# new_topology.net
KiCad netlist of a schematic drawn in Altium Designer
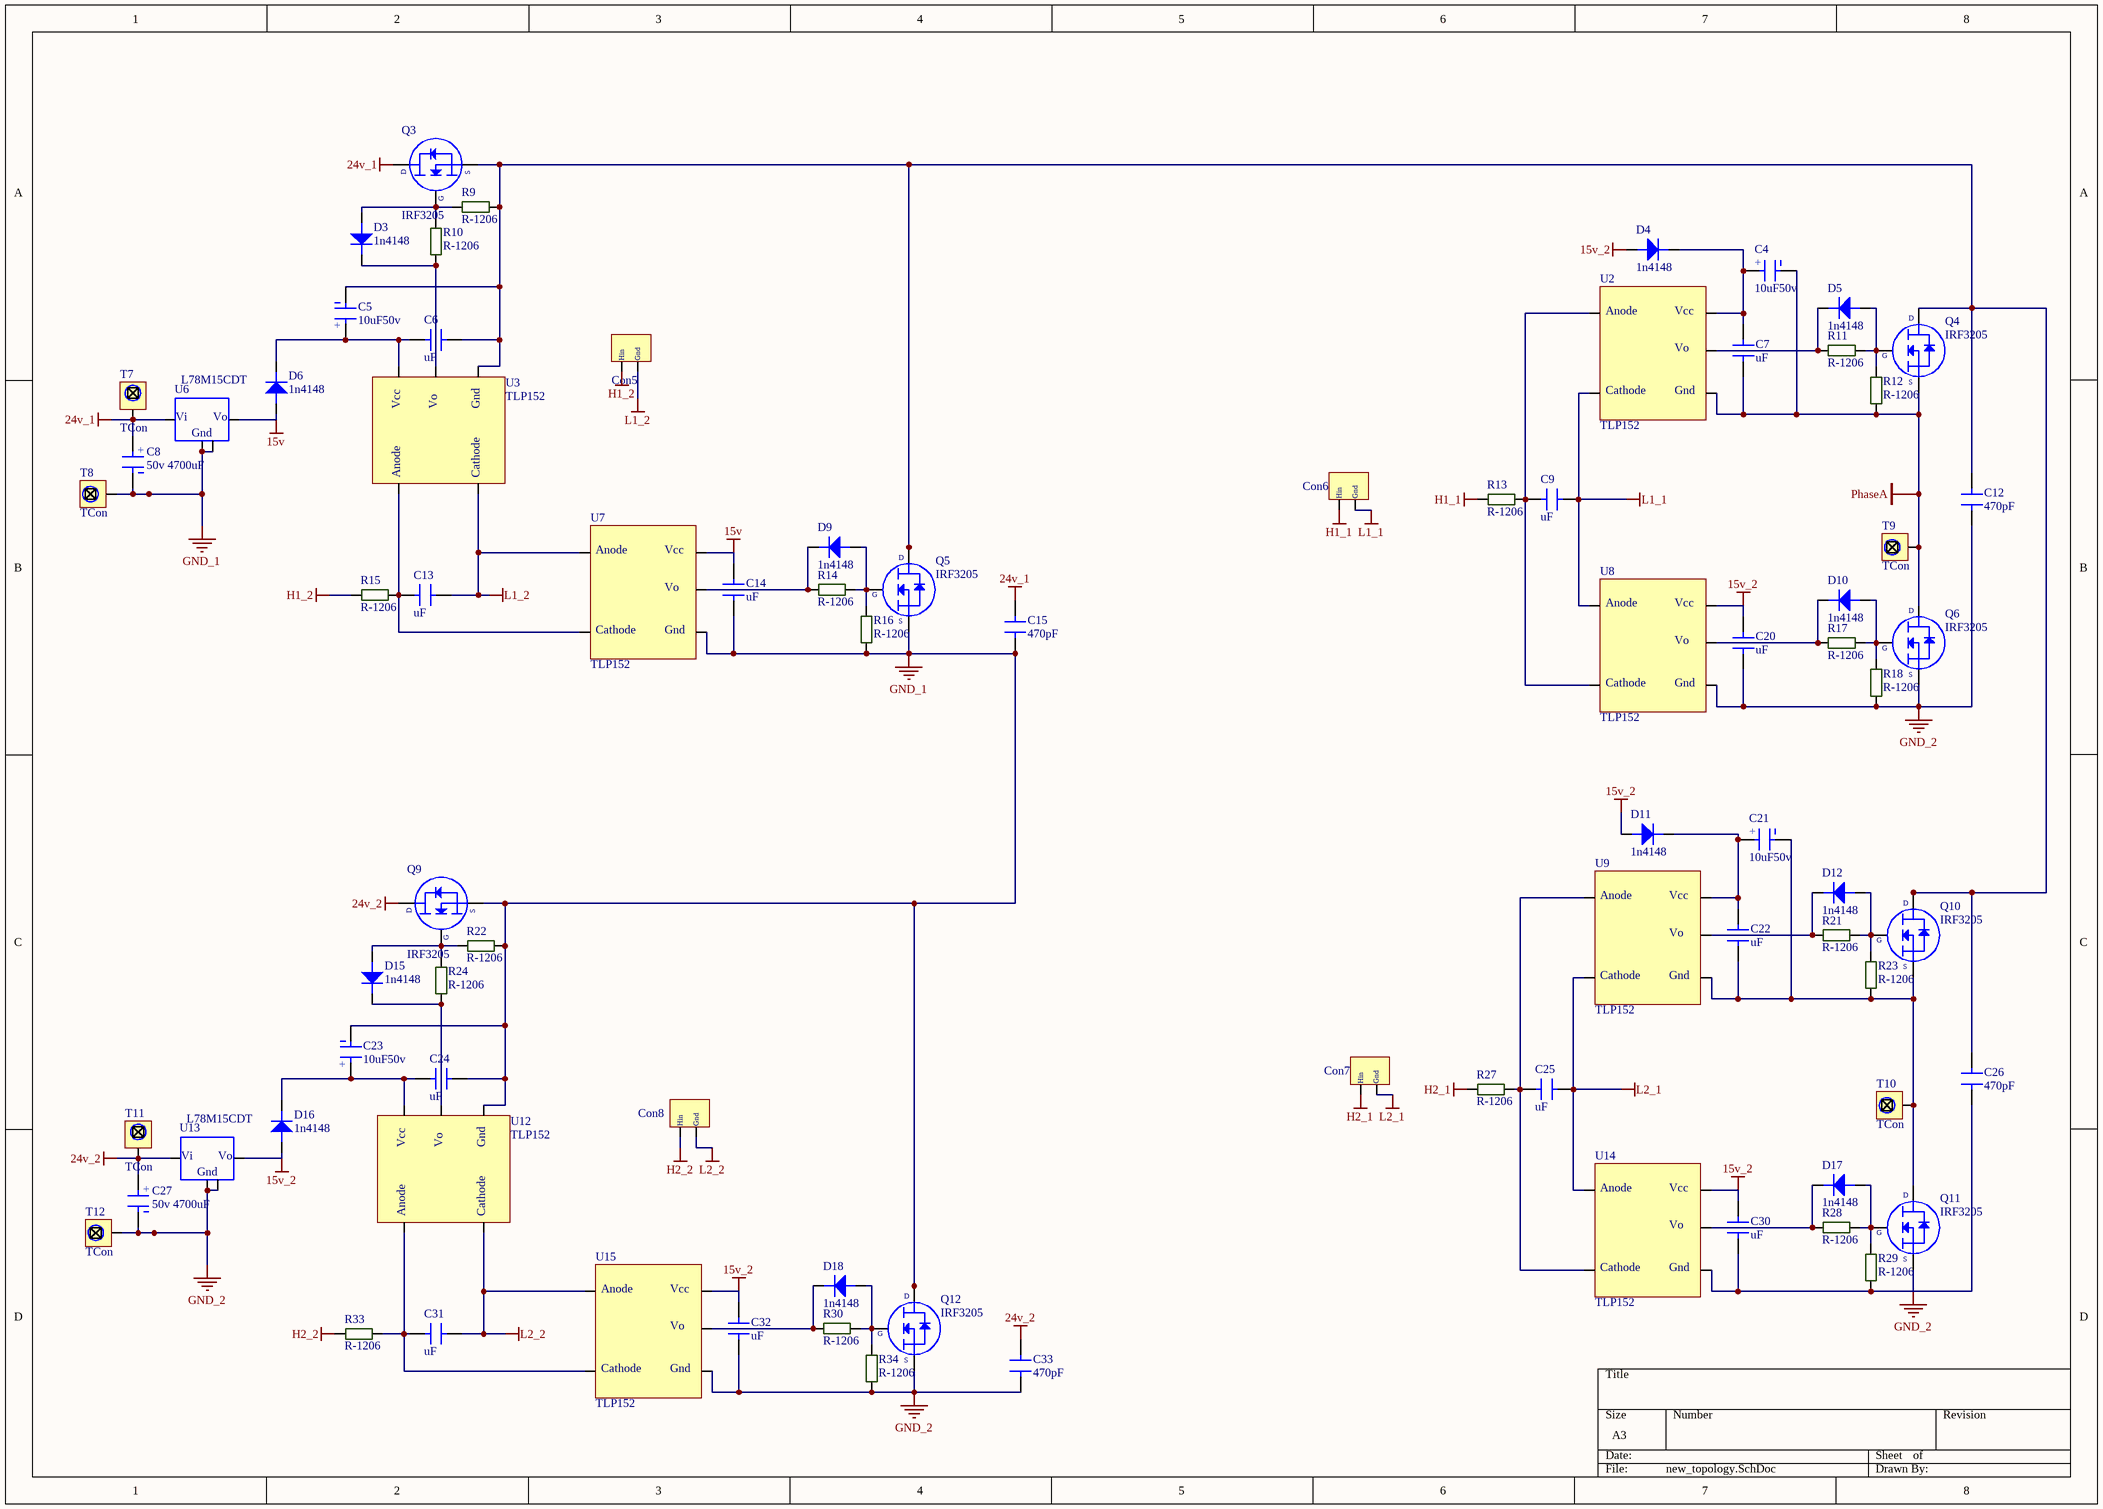
[diagram p0: new_topology.SchDoc]

(export (version "E")
  (design (tool "Eeschema 10.0.6"))
  (components
    (comp (ref "C4")
      (value "10uF50v")
      (footprint "ThreePhaseMLI:4x5.3 cap")
      (description "Aluminum Electrolytic Capacitors - SMD 50volts 10uF 6.3x5.8")
      (fields
        (field (name "MANUFACTURER") "Nichicon")
        (field (name "MANUFACTURER PART NUMBER") "UWD1H100MCL1GS")
      )
      (libsource (lib "ThreePhaseMLI") (part "UWD1H100MCL1GS"))
    )
    (comp (ref "C5")
      (value "10uF50v")
      (footprint "ThreePhaseMLI:4x5.3 cap")
      (description "Aluminum Electrolytic Capacitors - SMD 50volts 10uF 6.3x5.8")
      (fields
        (field (name "MANUFACTURER") "Nichicon")
        (field (name "MANUFACTURER PART NUMBER") "UWD1H100MCL1GS")
      )
      (libsource (lib "ThreePhaseMLI") (part "UWD1H100MCL1GS"))
    )
    (comp (ref "C6")
      (value "uF")
      (footprint "LFI Power Board PcbLib1:C-1206")
      (libsource (lib "ThreePhaseMLI") (part "C-1206"))
    )
    (comp (ref "C7")
      (value "uF")
      (footprint "LFI Power Board PcbLib1:C-1206")
      (libsource (lib "ThreePhaseMLI") (part "C-1206"))
    )
    (comp (ref "C8")
      (value "50v 4700uF")
      (footprint "ThreePhaseMLI:CAPPRD1000W190D2575H3200")
      (description "PKL5-063V472MM450 Aluminum Electrolytic Capacitors - Snap In 63volts 4700uF 20%")
      (fields
        (field (name "MANUFACTURER") "Nichicon")
        (field (name "MANUFACTURER PART NUMBER") "LKS1J472MESZ")
      )
      (libsource (lib "ThreePhaseMLI") (part "Aluminum Electrolytic Capacitors"))
    )
    (comp (ref "C9")
      (value "uF")
      (footprint "LFI Power Board PcbLib1:C-1206")
      (libsource (lib "ThreePhaseMLI") (part "C-1206"))
    )
    (comp (ref "C12")
      (value "470pF")
      (footprint "ThreePhaseMLI:100v 470pF")
      (libsource (lib "ThreePhaseMLI") (part "100v 470p cap"))
    )
    (comp (ref "C13")
      (value "uF")
      (footprint "LFI Power Board PcbLib1:C-1206")
      (libsource (lib "ThreePhaseMLI") (part "C-1206"))
    )
    (comp (ref "C14")
      (value "uF")
      (footprint "LFI Power Board PcbLib1:C-1206")
      (libsource (lib "ThreePhaseMLI") (part "C-1206"))
    )
    (comp (ref "C15")
      (value "470pF")
      (footprint "ThreePhaseMLI:100v 470pF")
      (libsource (lib "ThreePhaseMLI") (part "100v 470p cap"))
    )
    (comp (ref "C20")
      (value "uF")
      (footprint "LFI Power Board PcbLib1:C-1206")
      (libsource (lib "ThreePhaseMLI") (part "C-1206"))
    )
    (comp (ref "C21")
      (value "10uF50v")
      (footprint "ThreePhaseMLI:4x5.3 cap")
      (description "Aluminum Electrolytic Capacitors - SMD 50volts 10uF 6.3x5.8")
      (fields
        (field (name "MANUFACTURER") "Nichicon")
        (field (name "MANUFACTURER PART NUMBER") "UWD1H100MCL1GS")
      )
      (libsource (lib "ThreePhaseMLI") (part "UWD1H100MCL1GS"))
    )
    (comp (ref "C22")
      (value "uF")
      (footprint "LFI Power Board PcbLib1:C-1206")
      (libsource (lib "ThreePhaseMLI") (part "C-1206"))
    )
    (comp (ref "C23")
      (value "10uF50v")
      (footprint "ThreePhaseMLI:4x5.3 cap")
      (description "Aluminum Electrolytic Capacitors - SMD 50volts 10uF 6.3x5.8")
      (fields
        (field (name "MANUFACTURER") "Nichicon")
        (field (name "MANUFACTURER PART NUMBER") "UWD1H100MCL1GS")
      )
      (libsource (lib "ThreePhaseMLI") (part "UWD1H100MCL1GS"))
    )
    (comp (ref "C24")
      (value "uF")
      (footprint "LFI Power Board PcbLib1:C-1206")
      (libsource (lib "ThreePhaseMLI") (part "C-1206"))
    )
    (comp (ref "C25")
      (value "uF")
      (footprint "LFI Power Board PcbLib1:C-1206")
      (libsource (lib "ThreePhaseMLI") (part "C-1206"))
    )
    (comp (ref "C26")
      (value "470pF")
      (footprint "ThreePhaseMLI:100v 470pF")
      (libsource (lib "ThreePhaseMLI") (part "100v 470p cap"))
    )
    (comp (ref "C27")
      (value "50v 4700uF")
      (footprint "ThreePhaseMLI:CAPPRD1000W190D2575H3200")
      (description "PKL5-063V472MM450 Aluminum Electrolytic Capacitors - Snap In 63volts 4700uF 20%")
      (fields
        (field (name "MANUFACTURER") "Nichicon")
        (field (name "MANUFACTURER PART NUMBER") "LKS1J472MESZ")
      )
      (libsource (lib "ThreePhaseMLI") (part "Aluminum Electrolytic Capacitors"))
    )
    (comp (ref "C30")
      (value "uF")
      (footprint "LFI Power Board PcbLib1:C-1206")
      (libsource (lib "ThreePhaseMLI") (part "C-1206"))
    )
    (comp (ref "C31")
      (value "uF")
      (footprint "LFI Power Board PcbLib1:C-1206")
      (libsource (lib "ThreePhaseMLI") (part "C-1206"))
    )
    (comp (ref "C32")
      (value "uF")
      (footprint "LFI Power Board PcbLib1:C-1206")
      (libsource (lib "ThreePhaseMLI") (part "C-1206"))
    )
    (comp (ref "C33")
      (value "470pF")
      (footprint "ThreePhaseMLI:100v 470pF")
      (libsource (lib "ThreePhaseMLI") (part "100v 470p cap"))
    )
    (comp (ref "Con5")
      (value "Connector2")
      (footprint "Conn")
      (libsource (lib "ThreePhaseMLI") (part "Connector2"))
    )
    (comp (ref "Con6")
      (value "Connector2")
      (footprint "Conn")
      (libsource (lib "ThreePhaseMLI") (part "Connector2"))
    )
    (comp (ref "Con7")
      (value "Connector2")
      (footprint "Conn")
      (libsource (lib "ThreePhaseMLI") (part "Connector2"))
    )
    (comp (ref "Con8")
      (value "Connector2")
      (footprint "Conn")
      (libsource (lib "ThreePhaseMLI") (part "Connector2"))
    )
    (comp (ref "D3")
      (value "1n4148")
      (footprint "LFI Power Board PcbLib1:SOD123")
      (description "Diode Small Signal Switching 100V 0.15A 2-Pin SOD-123 T/R")
      (fields
        (field (name "MANUFACTURER") "Vishay")
        (field (name "MANUFACTURER PART NUMBER") "1N4148W-E3-18")
      )
      (libsource (lib "ThreePhaseMLI") (part "1N4148W-E3-18"))
    )
    (comp (ref "D4")
      (value "1n4148")
      (footprint "LFI Power Board PcbLib1:SOD123")
      (description "Diode Small Signal Switching 100V 0.15A 2-Pin SOD-123 T/R")
      (fields
        (field (name "MANUFACTURER") "Vishay")
        (field (name "MANUFACTURER PART NUMBER") "1N4148W-E3-18")
      )
      (libsource (lib "ThreePhaseMLI") (part "1N4148W-E3-18"))
    )
    (comp (ref "D5")
      (value "1n4148")
      (footprint "LFI Power Board PcbLib1:SOD123")
      (description "Diode Small Signal Switching 100V 0.15A 2-Pin SOD-123 T/R")
      (fields
        (field (name "MANUFACTURER") "Vishay")
        (field (name "MANUFACTURER PART NUMBER") "1N4148W-E3-18")
      )
      (libsource (lib "ThreePhaseMLI") (part "1N4148W-E3-18"))
    )
    (comp (ref "D6")
      (value "1n4148")
      (footprint "LFI Power Board PcbLib1:SOD123")
      (description "Diode Small Signal Switching 100V 0.15A 2-Pin SOD-123 T/R")
      (fields
        (field (name "MANUFACTURER") "Vishay")
        (field (name "MANUFACTURER PART NUMBER") "1N4148W-E3-18")
      )
      (libsource (lib "ThreePhaseMLI") (part "1N4148W-E3-18"))
    )
    (comp (ref "D9")
      (value "1n4148")
      (footprint "LFI Power Board PcbLib1:SOD123")
      (description "Diode Small Signal Switching 100V 0.15A 2-Pin SOD-123 T/R")
      (fields
        (field (name "MANUFACTURER") "Vishay")
        (field (name "MANUFACTURER PART NUMBER") "1N4148W-E3-18")
      )
      (libsource (lib "ThreePhaseMLI") (part "1N4148W-E3-18"))
    )
    (comp (ref "D10")
      (value "1n4148")
      (footprint "LFI Power Board PcbLib1:SOD123")
      (description "Diode Small Signal Switching 100V 0.15A 2-Pin SOD-123 T/R")
      (fields
        (field (name "MANUFACTURER") "Vishay")
        (field (name "MANUFACTURER PART NUMBER") "1N4148W-E3-18")
      )
      (libsource (lib "ThreePhaseMLI") (part "1N4148W-E3-18"))
    )
    (comp (ref "D11")
      (value "1n4148")
      (footprint "LFI Power Board PcbLib1:SOD123")
      (description "Diode Small Signal Switching 100V 0.15A 2-Pin SOD-123 T/R")
      (fields
        (field (name "MANUFACTURER") "Vishay")
        (field (name "MANUFACTURER PART NUMBER") "1N4148W-E3-18")
      )
      (libsource (lib "ThreePhaseMLI") (part "1N4148W-E3-18"))
    )
    (comp (ref "D12")
      (value "1n4148")
      (footprint "LFI Power Board PcbLib1:SOD123")
      (description "Diode Small Signal Switching 100V 0.15A 2-Pin SOD-123 T/R")
      (fields
        (field (name "MANUFACTURER") "Vishay")
        (field (name "MANUFACTURER PART NUMBER") "1N4148W-E3-18")
      )
      (libsource (lib "ThreePhaseMLI") (part "1N4148W-E3-18"))
    )
    (comp (ref "D15")
      (value "1n4148")
      (footprint "LFI Power Board PcbLib1:SOD123")
      (description "Diode Small Signal Switching 100V 0.15A 2-Pin SOD-123 T/R")
      (fields
        (field (name "MANUFACTURER") "Vishay")
        (field (name "MANUFACTURER PART NUMBER") "1N4148W-E3-18")
      )
      (libsource (lib "ThreePhaseMLI") (part "1N4148W-E3-18"))
    )
    (comp (ref "D16")
      (value "1n4148")
      (footprint "LFI Power Board PcbLib1:SOD123")
      (description "Diode Small Signal Switching 100V 0.15A 2-Pin SOD-123 T/R")
      (fields
        (field (name "MANUFACTURER") "Vishay")
        (field (name "MANUFACTURER PART NUMBER") "1N4148W-E3-18")
      )
      (libsource (lib "ThreePhaseMLI") (part "1N4148W-E3-18"))
    )
    (comp (ref "D17")
      (value "1n4148")
      (footprint "LFI Power Board PcbLib1:SOD123")
      (description "Diode Small Signal Switching 100V 0.15A 2-Pin SOD-123 T/R")
      (fields
        (field (name "MANUFACTURER") "Vishay")
        (field (name "MANUFACTURER PART NUMBER") "1N4148W-E3-18")
      )
      (libsource (lib "ThreePhaseMLI") (part "1N4148W-E3-18"))
    )
    (comp (ref "D18")
      (value "1n4148")
      (footprint "LFI Power Board PcbLib1:SOD123")
      (description "Diode Small Signal Switching 100V 0.15A 2-Pin SOD-123 T/R")
      (fields
        (field (name "MANUFACTURER") "Vishay")
        (field (name "MANUFACTURER PART NUMBER") "1N4148W-E3-18")
      )
      (libsource (lib "ThreePhaseMLI") (part "1N4148W-E3-18"))
    )
    (comp (ref "Q3")
      (value "IRF3205")
      (footprint "LFI Power Board PcbLib1:DPAK_TO263")
      (description "MOSFET N-CH 55V 110A D2PAK")
      (fields
        (field (name "MANUFACTURER") "Infineon")
        (field (name "MANUFACTURER PART NUMBER") "IRF3205STRLPBF")
      )
      (libsource (lib "ThreePhaseMLI") (part "IRF3205STRLPBF"))
    )
    (comp (ref "Q4")
      (value "IRF3205")
      (footprint "LFI Power Board PcbLib1:DPAK_TO263")
      (description "MOSFET N-CH 55V 110A D2PAK")
      (fields
        (field (name "MANUFACTURER") "Infineon")
        (field (name "MANUFACTURER PART NUMBER") "IRF3205STRLPBF")
      )
      (libsource (lib "ThreePhaseMLI") (part "IRF3205STRLPBF"))
    )
    (comp (ref "Q5")
      (value "IRF3205")
      (footprint "LFI Power Board PcbLib1:DPAK_TO263")
      (description "MOSFET N-CH 55V 110A D2PAK")
      (fields
        (field (name "MANUFACTURER") "Infineon")
        (field (name "MANUFACTURER PART NUMBER") "IRF3205STRLPBF")
      )
      (libsource (lib "ThreePhaseMLI") (part "IRF3205STRLPBF"))
    )
    (comp (ref "Q6")
      (value "IRF3205")
      (footprint "LFI Power Board PcbLib1:DPAK_TO263")
      (description "MOSFET N-CH 55V 110A D2PAK")
      (fields
        (field (name "MANUFACTURER") "Infineon")
        (field (name "MANUFACTURER PART NUMBER") "IRF3205STRLPBF")
      )
      (libsource (lib "ThreePhaseMLI") (part "IRF3205STRLPBF"))
    )
    (comp (ref "Q9")
      (value "IRF3205")
      (footprint "LFI Power Board PcbLib1:DPAK_TO263")
      (description "MOSFET N-CH 55V 110A D2PAK")
      (fields
        (field (name "MANUFACTURER") "Infineon")
        (field (name "MANUFACTURER PART NUMBER") "IRF3205STRLPBF")
      )
      (libsource (lib "ThreePhaseMLI") (part "IRF3205STRLPBF"))
    )
    (comp (ref "Q10")
      (value "IRF3205")
      (footprint "LFI Power Board PcbLib1:DPAK_TO263")
      (description "MOSFET N-CH 55V 110A D2PAK")
      (fields
        (field (name "MANUFACTURER") "Infineon")
        (field (name "MANUFACTURER PART NUMBER") "IRF3205STRLPBF")
      )
      (libsource (lib "ThreePhaseMLI") (part "IRF3205STRLPBF"))
    )
    (comp (ref "Q11")
      (value "IRF3205")
      (footprint "LFI Power Board PcbLib1:DPAK_TO263")
      (description "MOSFET N-CH 55V 110A D2PAK")
      (fields
        (field (name "MANUFACTURER") "Infineon")
        (field (name "MANUFACTURER PART NUMBER") "IRF3205STRLPBF")
      )
      (libsource (lib "ThreePhaseMLI") (part "IRF3205STRLPBF"))
    )
    (comp (ref "Q12")
      (value "IRF3205")
      (footprint "LFI Power Board PcbLib1:DPAK_TO263")
      (description "MOSFET N-CH 55V 110A D2PAK")
      (fields
        (field (name "MANUFACTURER") "Infineon")
        (field (name "MANUFACTURER PART NUMBER") "IRF3205STRLPBF")
      )
      (libsource (lib "ThreePhaseMLI") (part "IRF3205STRLPBF"))
    )
    (comp (ref "R9")
      (value "R-1206")
      (footprint "LFI Power Board PcbLib1:R-1206")
      (description "Res1206")
      (libsource (lib "ThreePhaseMLI") (part "R-1206"))
    )
    (comp (ref "R10")
      (value "R-1206")
      (footprint "LFI Power Board PcbLib1:R-1206")
      (description "Res1206")
      (libsource (lib "ThreePhaseMLI") (part "R-1206"))
    )
    (comp (ref "R11")
      (value "R-1206")
      (footprint "LFI Power Board PcbLib1:R-1206")
      (description "Res1206")
      (libsource (lib "ThreePhaseMLI") (part "R-1206"))
    )
    (comp (ref "R12")
      (value "R-1206")
      (footprint "LFI Power Board PcbLib1:R-1206")
      (description "Res1206")
      (libsource (lib "ThreePhaseMLI") (part "R-1206"))
    )
    (comp (ref "R13")
      (value "R-1206")
      (footprint "LFI Power Board PcbLib1:R-1206")
      (description "Res1206")
      (libsource (lib "ThreePhaseMLI") (part "R-1206"))
    )
    (comp (ref "R14")
      (value "R-1206")
      (footprint "LFI Power Board PcbLib1:R-1206")
      (description "Res1206")
      (libsource (lib "ThreePhaseMLI") (part "R-1206"))
    )
    (comp (ref "R15")
      (value "R-1206")
      (footprint "LFI Power Board PcbLib1:R-1206")
      (description "Res1206")
      (libsource (lib "ThreePhaseMLI") (part "R-1206"))
    )
    (comp (ref "R16")
      (value "R-1206")
      (footprint "LFI Power Board PcbLib1:R-1206")
      (description "Res1206")
      (libsource (lib "ThreePhaseMLI") (part "R-1206"))
    )
    (comp (ref "R17")
      (value "R-1206")
      (footprint "LFI Power Board PcbLib1:R-1206")
      (description "Res1206")
      (libsource (lib "ThreePhaseMLI") (part "R-1206"))
    )
    (comp (ref "R18")
      (value "R-1206")
      (footprint "LFI Power Board PcbLib1:R-1206")
      (description "Res1206")
      (libsource (lib "ThreePhaseMLI") (part "R-1206"))
    )
    (comp (ref "R21")
      (value "R-1206")
      (footprint "LFI Power Board PcbLib1:R-1206")
      (description "Res1206")
      (libsource (lib "ThreePhaseMLI") (part "R-1206"))
    )
    (comp (ref "R22")
      (value "R-1206")
      (footprint "LFI Power Board PcbLib1:R-1206")
      (description "Res1206")
      (libsource (lib "ThreePhaseMLI") (part "R-1206"))
    )
    (comp (ref "R23")
      (value "R-1206")
      (footprint "LFI Power Board PcbLib1:R-1206")
      (description "Res1206")
      (libsource (lib "ThreePhaseMLI") (part "R-1206"))
    )
    (comp (ref "R24")
      (value "R-1206")
      (footprint "LFI Power Board PcbLib1:R-1206")
      (description "Res1206")
      (libsource (lib "ThreePhaseMLI") (part "R-1206"))
    )
    (comp (ref "R27")
      (value "R-1206")
      (footprint "LFI Power Board PcbLib1:R-1206")
      (description "Res1206")
      (libsource (lib "ThreePhaseMLI") (part "R-1206"))
    )
    (comp (ref "R28")
      (value "R-1206")
      (footprint "LFI Power Board PcbLib1:R-1206")
      (description "Res1206")
      (libsource (lib "ThreePhaseMLI") (part "R-1206"))
    )
    (comp (ref "R29")
      (value "R-1206")
      (footprint "LFI Power Board PcbLib1:R-1206")
      (description "Res1206")
      (libsource (lib "ThreePhaseMLI") (part "R-1206"))
    )
    (comp (ref "R30")
      (value "R-1206")
      (footprint "LFI Power Board PcbLib1:R-1206")
      (description "Res1206")
      (libsource (lib "ThreePhaseMLI") (part "R-1206"))
    )
    (comp (ref "R33")
      (value "R-1206")
      (footprint "LFI Power Board PcbLib1:R-1206")
      (description "Res1206")
      (libsource (lib "ThreePhaseMLI") (part "R-1206"))
    )
    (comp (ref "R34")
      (value "R-1206")
      (footprint "LFI Power Board PcbLib1:R-1206")
      (description "Res1206")
      (libsource (lib "ThreePhaseMLI") (part "R-1206"))
    )
    (comp (ref "T7")
      (value "TCon")
      (footprint "LFI Power Board PcbLib1:tCon")
      (libsource (lib "ThreePhaseMLI") (part "Terminal Connector"))
    )
    (comp (ref "T8")
      (value "TCon")
      (footprint "LFI Power Board PcbLib1:tCon")
      (libsource (lib "") (part "Terminal Connector_1"))
    )
    (comp (ref "T9")
      (value "TCon")
      (footprint "LFI Power Board PcbLib1:tCon")
      (libsource (lib "") (part "Terminal Connector_1"))
    )
    (comp (ref "T10")
      (value "TCon")
      (footprint "LFI Power Board PcbLib1:tCon")
      (libsource (lib "") (part "Terminal Connector_1"))
    )
    (comp (ref "T11")
      (value "TCon")
      (footprint "LFI Power Board PcbLib1:tCon")
      (libsource (lib "ThreePhaseMLI") (part "Terminal Connector"))
    )
    (comp (ref "T12")
      (value "TCon")
      (footprint "LFI Power Board PcbLib1:tCon")
      (libsource (lib "") (part "Terminal Connector_1"))
    )
    (comp (ref "U2")
      (value "TLP152")
      (footprint "TLP152")
      (description "OPTOISO 3.75KV GATE DRIVER 6SO-5")
      (fields
        (field (name "MANUFACTURER") "Toshiba")
        (field (name "MANUFACTURER PART NUMBER") "TLP152(TPL,E")
      )
      (libsource (lib "ThreePhaseMLI") (part "TLP152(TPL,E"))
    )
    (comp (ref "U3")
      (value "TLP152")
      (footprint "TLP152")
      (description "OPTOISO 3.75KV GATE DRIVER 6SO-5")
      (fields
        (field (name "MANUFACTURER") "Toshiba")
        (field (name "MANUFACTURER PART NUMBER") "TLP152(TPL,E")
      )
      (libsource (lib "") (part "TLP152(TPL,E_1"))
    )
    (comp (ref "U6")
      (value "L78M15CDT")
      (footprint "ThreePhaseMLI:TO-252")
      (description "Linear Voltage Regulators 15V 0.5A Positive")
      (fields (field (name "MANUFACTURER") "STMicroelectronics"))
      (libsource (lib "ThreePhaseMLI") (part "L78M15CDT"))
    )
    (comp (ref "U7")
      (value "TLP152")
      (footprint "TLP152")
      (description "OPTOISO 3.75KV GATE DRIVER 6SO-5")
      (fields
        (field (name "MANUFACTURER") "Toshiba")
        (field (name "MANUFACTURER PART NUMBER") "TLP152(TPL,E")
      )
      (libsource (lib "ThreePhaseMLI") (part "TLP152(TPL,E"))
    )
    (comp (ref "U8")
      (value "TLP152")
      (footprint "TLP152")
      (description "OPTOISO 3.75KV GATE DRIVER 6SO-5")
      (fields
        (field (name "MANUFACTURER") "Toshiba")
        (field (name "MANUFACTURER PART NUMBER") "TLP152(TPL,E")
      )
      (libsource (lib "ThreePhaseMLI") (part "TLP152(TPL,E"))
    )
    (comp (ref "U9")
      (value "TLP152")
      (footprint "TLP152")
      (description "OPTOISO 3.75KV GATE DRIVER 6SO-5")
      (fields
        (field (name "MANUFACTURER") "Toshiba")
        (field (name "MANUFACTURER PART NUMBER") "TLP152(TPL,E")
      )
      (libsource (lib "ThreePhaseMLI") (part "TLP152(TPL,E"))
    )
    (comp (ref "U12")
      (value "TLP152")
      (footprint "TLP152")
      (description "OPTOISO 3.75KV GATE DRIVER 6SO-5")
      (fields
        (field (name "MANUFACTURER") "Toshiba")
        (field (name "MANUFACTURER PART NUMBER") "TLP152(TPL,E")
      )
      (libsource (lib "") (part "TLP152(TPL,E_1"))
    )
    (comp (ref "U13")
      (value "L78M15CDT")
      (footprint "ThreePhaseMLI:TO-252")
      (description "Linear Voltage Regulators 15V 0.5A Positive")
      (fields (field (name "MANUFACTURER") "STMicroelectronics"))
      (libsource (lib "ThreePhaseMLI") (part "L78M15CDT"))
    )
    (comp (ref "U14")
      (value "TLP152")
      (footprint "TLP152")
      (description "OPTOISO 3.75KV GATE DRIVER 6SO-5")
      (fields
        (field (name "MANUFACTURER") "Toshiba")
        (field (name "MANUFACTURER PART NUMBER") "TLP152(TPL,E")
      )
      (libsource (lib "ThreePhaseMLI") (part "TLP152(TPL,E"))
    )
    (comp (ref "U15")
      (value "TLP152")
      (footprint "TLP152")
      (description "OPTOISO 3.75KV GATE DRIVER 6SO-5")
      (fields
        (field (name "MANUFACTURER") "Toshiba")
        (field (name "MANUFACTURER PART NUMBER") "TLP152(TPL,E")
      )
      (libsource (lib "ThreePhaseMLI") (part "TLP152(TPL,E"))
    )
  )
  (nets
    (net (code "1") (name "15v") (class "Default")
      (node (ref "C14") (pin "2") (pinfunction "2_2") (pintype "passive"))
      (node (ref "D6") (pin "a") (pinfunction "a_a") (pintype "passive"))
      (node (ref "U6") (pin "3") (pinfunction "3_3") (pintype "passive"))
      (node (ref "U7") (pin "5") (pinfunction "5_5") (pintype "passive"))
    )
    (net (code "2") (name "15v_2") (class "Default")
      (node (ref "C20") (pin "2") (pinfunction "2_2") (pintype "passive"))
      (node (ref "C30") (pin "2") (pinfunction "2_2") (pintype "passive"))
      (node (ref "C32") (pin "2") (pinfunction "2_2") (pintype "passive"))
      (node (ref "D11") (pin "a") (pinfunction "a_a") (pintype "passive"))
      (node (ref "D16") (pin "a") (pinfunction "a_a") (pintype "passive"))
      (node (ref "D4") (pin "a") (pinfunction "a_a") (pintype "passive"))
      (node (ref "U13") (pin "3") (pinfunction "3_3") (pintype "passive"))
      (node (ref "U14") (pin "5") (pinfunction "5_5") (pintype "passive"))
      (node (ref "U15") (pin "5") (pinfunction "5_5") (pintype "passive"))
      (node (ref "U8") (pin "5") (pinfunction "5_5") (pintype "passive"))
    )
    (net (code "3") (name "24v_1") (class "Default")
      (node (ref "C15") (pin "1") (pinfunction "1_1") (pintype "passive"))
      (node (ref "C8") (pin "2") (pinfunction "2_2") (pintype "passive"))
      (node (ref "Q3") (pin "3") (pinfunction "3_3") (pintype "passive"))
      (node (ref "T7") (pin "1") (pinfunction "1_1") (pintype "passive"))
      (node (ref "U6") (pin "1") (pinfunction "1_1") (pintype "passive"))
    )
    (net (code "4") (name "24v_2") (class "Default")
      (node (ref "C27") (pin "2") (pinfunction "2_2") (pintype "passive"))
      (node (ref "C33") (pin "1") (pinfunction "1_1") (pintype "passive"))
      (node (ref "Q9") (pin "3") (pinfunction "3_3") (pintype "passive"))
      (node (ref "T11") (pin "1") (pinfunction "1_1") (pintype "passive"))
      (node (ref "U13") (pin "1") (pinfunction "1_1") (pintype "passive"))
    )
    (net (code "5") (name "GND_1") (class "Default")
      (node (ref "C14") (pin "1") (pinfunction "1_1") (pintype "passive"))
      (node (ref "C15") (pin "2") (pinfunction "2_2") (pintype "passive"))
      (node (ref "C23") (pin "2") (pinfunction "2_2") (pintype "passive"))
      (node (ref "C24") (pin "1") (pinfunction "1_1") (pintype "passive"))
      (node (ref "C8") (pin "1") (pinfunction "1_1") (pintype "passive"))
      (node (ref "Q12") (pin "3") (pinfunction "3_3") (pintype "passive"))
      (node (ref "Q5") (pin "2") (pinfunction "2_2") (pintype "passive"))
      (node (ref "Q9") (pin "2") (pinfunction "2_2") (pintype "passive"))
      (node (ref "R16") (pin "1") (pinfunction "1_1") (pintype "passive"))
      (node (ref "R22") (pin "1") (pinfunction "1_1") (pintype "passive"))
      (node (ref "T8") (pin "1") (pinfunction "1_1") (pintype "passive"))
      (node (ref "U12") (pin "3") (pinfunction "3_3") (pintype "passive"))
      (node (ref "U6") (pin "2") (pinfunction "2_2") (pintype "passive"))
      (node (ref "U6") (pin "4") (pinfunction "4_4") (pintype "passive"))
      (node (ref "U7") (pin "3") (pinfunction "3_3") (pintype "passive"))
    )
    (net (code "6") (name "GND_2") (class "Default")
      (node (ref "C12") (pin "1") (pinfunction "1_1") (pintype "passive"))
      (node (ref "C20") (pin "1") (pinfunction "1_1") (pintype "passive"))
      (node (ref "C26") (pin "1") (pinfunction "1_1") (pintype "passive"))
      (node (ref "C27") (pin "1") (pinfunction "1_1") (pintype "passive"))
      (node (ref "C30") (pin "1") (pinfunction "1_1") (pintype "passive"))
      (node (ref "C32") (pin "1") (pinfunction "1_1") (pintype "passive"))
      (node (ref "C33") (pin "2") (pinfunction "2_2") (pintype "passive"))
      (node (ref "Q11") (pin "2") (pinfunction "2_2") (pintype "passive"))
      (node (ref "Q12") (pin "2") (pinfunction "2_2") (pintype "passive"))
      (node (ref "Q6") (pin "2") (pinfunction "2_2") (pintype "passive"))
      (node (ref "R18") (pin "1") (pinfunction "1_1") (pintype "passive"))
      (node (ref "R29") (pin "1") (pinfunction "1_1") (pintype "passive"))
      (node (ref "R34") (pin "1") (pinfunction "1_1") (pintype "passive"))
      (node (ref "T12") (pin "1") (pinfunction "1_1") (pintype "passive"))
      (node (ref "U13") (pin "2") (pinfunction "2_2") (pintype "passive"))
      (node (ref "U13") (pin "4") (pinfunction "4_4") (pintype "passive"))
      (node (ref "U14") (pin "3") (pinfunction "3_3") (pintype "passive"))
      (node (ref "U15") (pin "3") (pinfunction "3_3") (pintype "passive"))
      (node (ref "U8") (pin "3") (pinfunction "3_3") (pintype "passive"))
    )
    (net (code "7") (name "H1_1") (class "Default")
      (node (ref "Con6") (pin "1") (pinfunction "1_1") (pintype "passive"))
      (node (ref "R13") (pin "1") (pinfunction "1_1") (pintype "passive"))
    )
    (net (code "8") (name "H1_2") (class "Default")
      (node (ref "Con5") (pin "1") (pinfunction "1_1") (pintype "passive"))
      (node (ref "R15") (pin "1") (pinfunction "1_1") (pintype "passive"))
    )
    (net (code "9") (name "H2_1") (class "Default")
      (node (ref "Con7") (pin "1") (pinfunction "1_1") (pintype "passive"))
      (node (ref "R27") (pin "1") (pinfunction "1_1") (pintype "passive"))
    )
    (net (code "10") (name "H2_2") (class "Default")
      (node (ref "Con8") (pin "1") (pinfunction "1_1") (pintype "passive"))
      (node (ref "R33") (pin "1") (pinfunction "1_1") (pintype "passive"))
    )
    (net (code "11") (name "L1_1") (class "Default")
      (node (ref "C9") (pin "2") (pinfunction "2_2") (pintype "passive"))
      (node (ref "Con6") (pin "2") (pinfunction "2_2") (pintype "passive"))
      (node (ref "U2") (pin "2") (pinfunction "2_2") (pintype "passive"))
      (node (ref "U8") (pin "1") (pinfunction "1_1") (pintype "passive"))
    )
    (net (code "12") (name "L1_2") (class "Default")
      (node (ref "C13") (pin "2") (pinfunction "2_2") (pintype "passive"))
      (node (ref "Con5") (pin "2") (pinfunction "2_2") (pintype "passive"))
      (node (ref "U3") (pin "2") (pinfunction "2_2") (pintype "passive"))
      (node (ref "U7") (pin "1") (pinfunction "1_1") (pintype "passive"))
    )
    (net (code "13") (name "L2_1") (class "Default")
      (node (ref "C25") (pin "2") (pinfunction "2_2") (pintype "passive"))
      (node (ref "Con7") (pin "2") (pinfunction "2_2") (pintype "passive"))
      (node (ref "U14") (pin "1") (pinfunction "1_1") (pintype "passive"))
      (node (ref "U9") (pin "2") (pinfunction "2_2") (pintype "passive"))
    )
    (net (code "14") (name "L2_2") (class "Default")
      (node (ref "C31") (pin "2") (pinfunction "2_2") (pintype "passive"))
      (node (ref "Con8") (pin "2") (pinfunction "2_2") (pintype "passive"))
      (node (ref "U12") (pin "2") (pinfunction "2_2") (pintype "passive"))
      (node (ref "U15") (pin "1") (pinfunction "1_1") (pintype "passive"))
    )
    (net (code "15") (name "Net-(C4-Pad1)") (class "Default")
      (node (ref "C4") (pin "1") (pinfunction "1_1") (pintype "passive"))
      (node (ref "C7") (pin "2") (pinfunction "2_2") (pintype "passive"))
      (node (ref "D4") (pin "k") (pinfunction "k_k") (pintype "passive"))
      (node (ref "U2") (pin "5") (pinfunction "5_5") (pintype "passive"))
    )
    (net (code "16") (name "Net-(C5-Pad1)") (class "Default")
      (node (ref "C5") (pin "1") (pinfunction "1_1") (pintype "passive"))
      (node (ref "C6") (pin "2") (pinfunction "2_2") (pintype "passive"))
      (node (ref "D6") (pin "k") (pinfunction "k_k") (pintype "passive"))
      (node (ref "U3") (pin "5") (pinfunction "5_5") (pintype "passive"))
    )
    (net (code "17") (name "Net-(C9-Pad1)") (class "Default")
      (node (ref "C9") (pin "1") (pinfunction "1_1") (pintype "passive"))
      (node (ref "R13") (pin "2") (pinfunction "2_2") (pintype "passive"))
      (node (ref "U2") (pin "1") (pinfunction "1_1") (pintype "passive"))
      (node (ref "U8") (pin "2") (pinfunction "2_2") (pintype "passive"))
    )
    (net (code "18") (name "Net-(C12-Pad2)") (class "Default")
      (node (ref "C12") (pin "2") (pinfunction "2_2") (pintype "passive"))
      (node (ref "C26") (pin "2") (pinfunction "2_2") (pintype "passive"))
      (node (ref "C5") (pin "2") (pinfunction "2_2") (pintype "passive"))
      (node (ref "C6") (pin "1") (pinfunction "1_1") (pintype "passive"))
      (node (ref "Q10") (pin "3") (pinfunction "3_3") (pintype "passive"))
      (node (ref "Q3") (pin "2") (pinfunction "2_2") (pintype "passive"))
      (node (ref "Q4") (pin "3") (pinfunction "3_3") (pintype "passive"))
      (node (ref "Q5") (pin "3") (pinfunction "3_3") (pintype "passive"))
      (node (ref "R9") (pin "1") (pinfunction "1_1") (pintype "passive"))
      (node (ref "U3") (pin "3") (pinfunction "3_3") (pintype "passive"))
    )
    (net (code "19") (name "Net-(C13-Pad1)") (class "Default")
      (node (ref "C13") (pin "1") (pinfunction "1_1") (pintype "passive"))
      (node (ref "R15") (pin "2") (pinfunction "2_2") (pintype "passive"))
      (node (ref "U3") (pin "1") (pinfunction "1_1") (pintype "passive"))
      (node (ref "U7") (pin "2") (pinfunction "2_2") (pintype "passive"))
    )
    (net (code "20") (name "Net-(C21-Pad1)") (class "Default")
      (node (ref "C21") (pin "1") (pinfunction "1_1") (pintype "passive"))
      (node (ref "C22") (pin "2") (pinfunction "2_2") (pintype "passive"))
      (node (ref "D11") (pin "k") (pinfunction "k_k") (pintype "passive"))
      (node (ref "U9") (pin "5") (pinfunction "5_5") (pintype "passive"))
    )
    (net (code "21") (name "Net-(C21-Pad2)") (class "Default")
      (node (ref "C21") (pin "2") (pinfunction "2_2") (pintype "passive"))
      (node (ref "C22") (pin "1") (pinfunction "1_1") (pintype "passive"))
      (node (ref "Q10") (pin "2") (pinfunction "2_2") (pintype "passive"))
      (node (ref "Q11") (pin "3") (pinfunction "3_3") (pintype "passive"))
      (node (ref "R23") (pin "1") (pinfunction "1_1") (pintype "passive"))
      (node (ref "T10") (pin "1") (pinfunction "1_1") (pintype "passive"))
      (node (ref "U9") (pin "3") (pinfunction "3_3") (pintype "passive"))
    )
    (net (code "22") (name "Net-(C23-Pad1)") (class "Default")
      (node (ref "C23") (pin "1") (pinfunction "1_1") (pintype "passive"))
      (node (ref "C24") (pin "2") (pinfunction "2_2") (pintype "passive"))
      (node (ref "D16") (pin "k") (pinfunction "k_k") (pintype "passive"))
      (node (ref "U12") (pin "5") (pinfunction "5_5") (pintype "passive"))
    )
    (net (code "23") (name "Net-(C25-Pad1)") (class "Default")
      (node (ref "C25") (pin "1") (pinfunction "1_1") (pintype "passive"))
      (node (ref "R27") (pin "2") (pinfunction "2_2") (pintype "passive"))
      (node (ref "U14") (pin "2") (pinfunction "2_2") (pintype "passive"))
      (node (ref "U9") (pin "1") (pinfunction "1_1") (pintype "passive"))
    )
    (net (code "24") (name "Net-(C31-Pad1)") (class "Default")
      (node (ref "C31") (pin "1") (pinfunction "1_1") (pintype "passive"))
      (node (ref "R33") (pin "2") (pinfunction "2_2") (pintype "passive"))
      (node (ref "U12") (pin "1") (pinfunction "1_1") (pintype "passive"))
      (node (ref "U15") (pin "2") (pinfunction "2_2") (pintype "passive"))
    )
    (net (code "25") (name "Net-(D3-Pada)") (class "Default")
      (node (ref "D3") (pin "a") (pinfunction "a_a") (pintype "passive"))
      (node (ref "Q3") (pin "1") (pinfunction "1_1") (pintype "passive"))
      (node (ref "R10") (pin "2") (pinfunction "2_2") (pintype "passive"))
      (node (ref "R9") (pin "2") (pinfunction "2_2") (pintype "passive"))
    )
    (net (code "26") (name "Net-(D3-Padk)") (class "Default")
      (node (ref "D3") (pin "k") (pinfunction "k_k") (pintype "passive"))
      (node (ref "R10") (pin "1") (pinfunction "1_1") (pintype "passive"))
      (node (ref "U3") (pin "4") (pinfunction "4_4") (pintype "passive"))
    )
    (net (code "27") (name "Net-(D5-Pada)") (class "Default")
      (node (ref "D5") (pin "a") (pinfunction "a_a") (pintype "passive"))
      (node (ref "Q4") (pin "1") (pinfunction "1_1") (pintype "passive"))
      (node (ref "R11") (pin "2") (pinfunction "2_2") (pintype "passive"))
      (node (ref "R12") (pin "2") (pinfunction "2_2") (pintype "passive"))
    )
    (net (code "28") (name "Net-(D5-Padk)") (class "Default")
      (node (ref "D5") (pin "k") (pinfunction "k_k") (pintype "passive"))
      (node (ref "R11") (pin "1") (pinfunction "1_1") (pintype "passive"))
      (node (ref "U2") (pin "4") (pinfunction "4_4") (pintype "passive"))
    )
    (net (code "29") (name "Net-(D9-Pada)") (class "Default")
      (node (ref "D9") (pin "a") (pinfunction "a_a") (pintype "passive"))
      (node (ref "Q5") (pin "1") (pinfunction "1_1") (pintype "passive"))
      (node (ref "R14") (pin "2") (pinfunction "2_2") (pintype "passive"))
      (node (ref "R16") (pin "2") (pinfunction "2_2") (pintype "passive"))
    )
    (net (code "30") (name "Net-(D9-Padk)") (class "Default")
      (node (ref "D9") (pin "k") (pinfunction "k_k") (pintype "passive"))
      (node (ref "R14") (pin "1") (pinfunction "1_1") (pintype "passive"))
      (node (ref "U7") (pin "4") (pinfunction "4_4") (pintype "passive"))
    )
    (net (code "31") (name "Net-(D10-Pada)") (class "Default")
      (node (ref "D10") (pin "a") (pinfunction "a_a") (pintype "passive"))
      (node (ref "Q6") (pin "1") (pinfunction "1_1") (pintype "passive"))
      (node (ref "R17") (pin "2") (pinfunction "2_2") (pintype "passive"))
      (node (ref "R18") (pin "2") (pinfunction "2_2") (pintype "passive"))
    )
    (net (code "32") (name "Net-(D10-Padk)") (class "Default")
      (node (ref "D10") (pin "k") (pinfunction "k_k") (pintype "passive"))
      (node (ref "R17") (pin "1") (pinfunction "1_1") (pintype "passive"))
      (node (ref "U8") (pin "4") (pinfunction "4_4") (pintype "passive"))
    )
    (net (code "33") (name "Net-(D12-Pada)") (class "Default")
      (node (ref "D12") (pin "a") (pinfunction "a_a") (pintype "passive"))
      (node (ref "Q10") (pin "1") (pinfunction "1_1") (pintype "passive"))
      (node (ref "R21") (pin "2") (pinfunction "2_2") (pintype "passive"))
      (node (ref "R23") (pin "2") (pinfunction "2_2") (pintype "passive"))
    )
    (net (code "34") (name "Net-(D12-Padk)") (class "Default")
      (node (ref "D12") (pin "k") (pinfunction "k_k") (pintype "passive"))
      (node (ref "R21") (pin "1") (pinfunction "1_1") (pintype "passive"))
      (node (ref "U9") (pin "4") (pinfunction "4_4") (pintype "passive"))
    )
    (net (code "35") (name "Net-(D15-Pada)") (class "Default")
      (node (ref "D15") (pin "a") (pinfunction "a_a") (pintype "passive"))
      (node (ref "Q9") (pin "1") (pinfunction "1_1") (pintype "passive"))
      (node (ref "R22") (pin "2") (pinfunction "2_2") (pintype "passive"))
      (node (ref "R24") (pin "2") (pinfunction "2_2") (pintype "passive"))
    )
    (net (code "36") (name "Net-(D15-Padk)") (class "Default")
      (node (ref "D15") (pin "k") (pinfunction "k_k") (pintype "passive"))
      (node (ref "R24") (pin "1") (pinfunction "1_1") (pintype "passive"))
      (node (ref "U12") (pin "4") (pinfunction "4_4") (pintype "passive"))
    )
    (net (code "37") (name "Net-(D17-Pada)") (class "Default")
      (node (ref "D17") (pin "a") (pinfunction "a_a") (pintype "passive"))
      (node (ref "Q11") (pin "1") (pinfunction "1_1") (pintype "passive"))
      (node (ref "R28") (pin "2") (pinfunction "2_2") (pintype "passive"))
      (node (ref "R29") (pin "2") (pinfunction "2_2") (pintype "passive"))
    )
    (net (code "38") (name "Net-(D17-Padk)") (class "Default")
      (node (ref "D17") (pin "k") (pinfunction "k_k") (pintype "passive"))
      (node (ref "R28") (pin "1") (pinfunction "1_1") (pintype "passive"))
      (node (ref "U14") (pin "4") (pinfunction "4_4") (pintype "passive"))
    )
    (net (code "39") (name "Net-(D18-Pada)") (class "Default")
      (node (ref "D18") (pin "a") (pinfunction "a_a") (pintype "passive"))
      (node (ref "Q12") (pin "1") (pinfunction "1_1") (pintype "passive"))
      (node (ref "R30") (pin "2") (pinfunction "2_2") (pintype "passive"))
      (node (ref "R34") (pin "2") (pinfunction "2_2") (pintype "passive"))
    )
    (net (code "40") (name "Net-(D18-Padk)") (class "Default")
      (node (ref "D18") (pin "k") (pinfunction "k_k") (pintype "passive"))
      (node (ref "R30") (pin "1") (pinfunction "1_1") (pintype "passive"))
      (node (ref "U15") (pin "4") (pinfunction "4_4") (pintype "passive"))
    )
    (net (code "41") (name "PhaseA") (class "Default")
      (node (ref "C4") (pin "2") (pinfunction "2_2") (pintype "passive"))
      (node (ref "C7") (pin "1") (pinfunction "1_1") (pintype "passive"))
      (node (ref "Q4") (pin "2") (pinfunction "2_2") (pintype "passive"))
      (node (ref "Q6") (pin "3") (pinfunction "3_3") (pintype "passive"))
      (node (ref "R12") (pin "1") (pinfunction "1_1") (pintype "passive"))
      (node (ref "T9") (pin "1") (pinfunction "1_1") (pintype "passive"))
      (node (ref "U2") (pin "3") (pinfunction "3_3") (pintype "passive"))
    )
  )
)
